# VCCINT_IO_BRAM_PS.net
KiCad netlist of a schematic drawn in Altium Designer
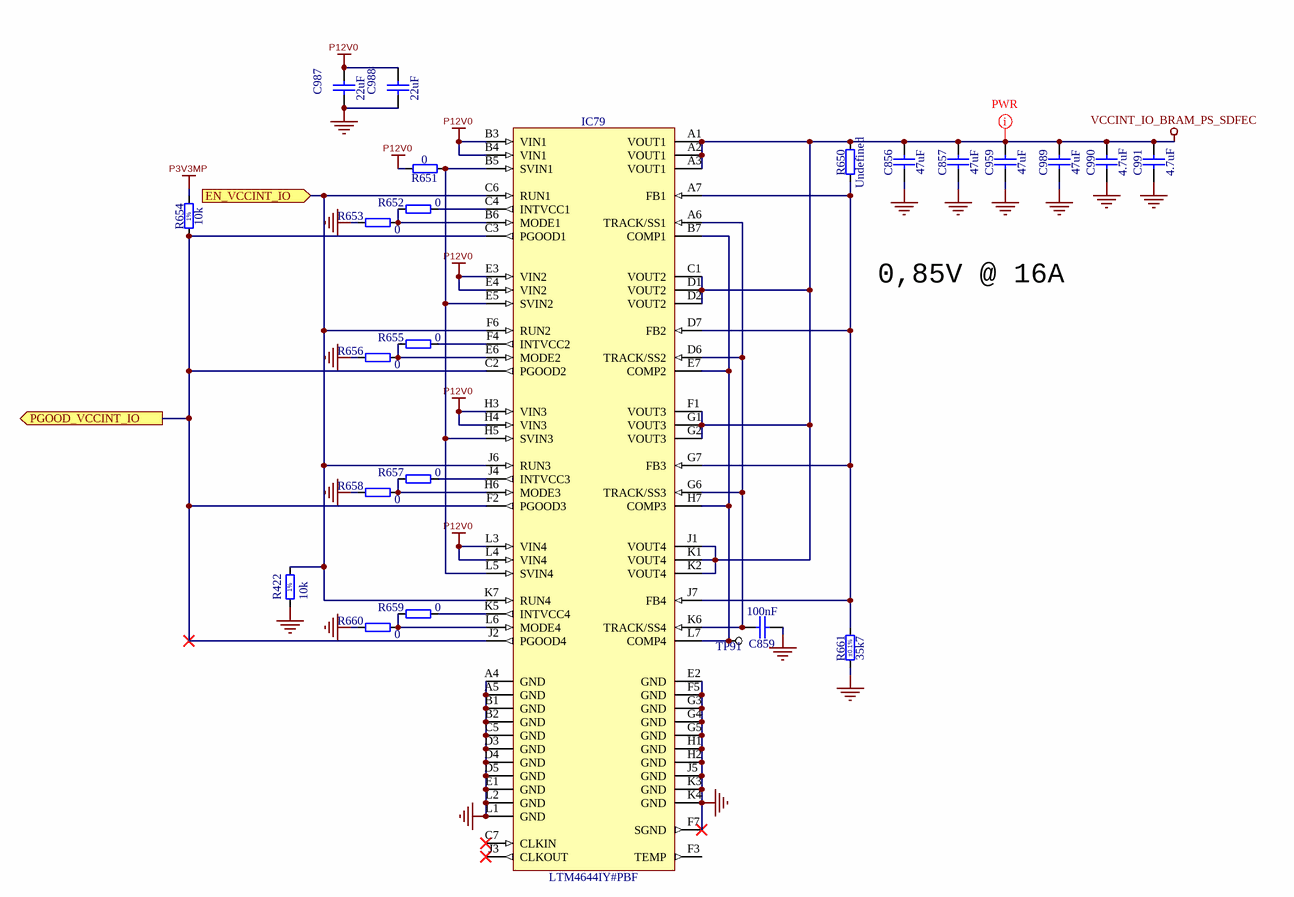
[diagram p0: VCCINT_IO_BRAM_PS.SchDoc]

(export (version "E")
  (design (tool "Eeschema 10.0.6"))
  (components
    (comp (ref "C856")
      (value "47uF")
      (footprint "CAPC2012X140N")
      (description "Non-polarised capacitor")
      (fields
        (field (name "MANUFACTURER PART NUMBER") "CC0805_47UF_6.3V_20%_X5R")
        (field (name "MANUFACTURER") "GENERIC")
        (field (name "AUTHOR") "CERN DEM JLC")
      )
      (libsource (lib "Capacitors") (part "Capacitor - non polarized"))
    )
    (comp (ref "C857")
      (value "47uF")
      (footprint "CAPC2012X140N")
      (description "Non-polarised capacitor")
      (fields
        (field (name "MANUFACTURER PART NUMBER") "CC0805_47UF_6.3V_20%_X5R")
        (field (name "MANUFACTURER") "GENERIC")
        (field (name "AUTHOR") "CERN DEM JLC")
      )
      (libsource (lib "Capacitors") (part "Capacitor - non polarized"))
    )
    (comp (ref "C859")
      (value "100nF")
      (footprint "CAPC1005X55N")
      (description "Non-polarised capacitor")
      (fields
        (field (name "PART NUMBER") "CC0402_100NF_16V_10%_X5R")
        (field (name "VOLTAGE") "16V")
        (field (name "AUTHOR") "CERN DEM JLC")
      )
      (libsource (lib "Capacitors") (part "Capacitor - non polarized"))
    )
    (comp (ref "C959")
      (value "47uF")
      (footprint "CAPC2012X140N")
      (description "Non-polarised capacitor")
      (fields
        (field (name "MANUFACTURER PART NUMBER") "CC0805_47UF_6.3V_20%_X5R")
        (field (name "MANUFACTURER") "GENERIC")
        (field (name "AUTHOR") "CERN DEM JLC")
      )
      (libsource (lib "Capacitors") (part "Capacitor - non polarized"))
    )
    (comp (ref "C987")
      (value "22uF")
      (footprint "CAPC2012X135N")
      (description "Non-polarised capacitor")
      (fields
        (field (name "MANUFACTURER PART NUMBER") "CC0805_22UF_16V_10%_X5R")
        (field (name "MANUFACTURER") "GENERIC")
        (field (name "AUTHOR") "CERN DEM JLC")
      )
      (libsource (lib "Capacitors") (part "Capacitor - non polarized"))
    )
    (comp (ref "C988")
      (value "22uF")
      (footprint "CAPC2012X135N")
      (description "Non-polarised capacitor")
      (fields
        (field (name "MANUFACTURER PART NUMBER") "CC0805_22UF_16V_10%_X5R")
        (field (name "MANUFACTURER") "GENERIC")
        (field (name "AUTHOR") "CERN DEM JLC")
      )
      (libsource (lib "Capacitors") (part "Capacitor - non polarized"))
    )
    (comp (ref "C989")
      (value "47uF")
      (footprint "CAPC2012X140N")
      (description "Non-polarised capacitor")
      (fields
        (field (name "MANUFACTURER PART NUMBER") "CC0805_47UF_6.3V_20%_X5R")
        (field (name "MANUFACTURER") "GENERIC")
        (field (name "AUTHOR") "CERN DEM JLC")
      )
      (libsource (lib "Capacitors") (part "Capacitor - non polarized"))
    )
    (comp (ref "C990")
      (value "4.7uF")
      (footprint "CAPC1709X95N")
      (description "Non-polarised capacitor")
      (fields
        (field (name "MANUFACTURER PART NUMBER") "CC0603_4.7UF_16V_10%_X5R")
        (field (name "MANUFACTURER") "GENERIC")
        (field (name "AUTHOR") "CERN DEM JLC")
      )
      (libsource (lib "Capacitors") (part "Capacitor - non polarized"))
    )
    (comp (ref "C991")
      (value "4.7uF")
      (footprint "CAPC1709X95N")
      (description "Non-polarised capacitor")
      (fields
        (field (name "MANUFACTURER PART NUMBER") "CC0603_4.7UF_16V_10%_X5R")
        (field (name "MANUFACTURER") "GENERIC")
        (field (name "AUTHOR") "CERN DEM JLC")
      )
      (libsource (lib "Capacitors") (part "Capacitor - non polarized"))
    )
    (comp (ref "IC79")
      (value "LTM4644IY#PBF")
      (footprint "BGA77C127P7X11_900X1500X521")
      (description "Quad DC/DC µModule Regulator with Configurable 4A Output Array")
      (fields (field (name "MANUFACTURER") "LINEAR TECHNOLOGY") (field (name "AUTHOR") "CERN DEM JLC"))
      (libsource (lib "ICs And Semiconductors") (part "LTM4644"))
    )
    (comp (ref "R422")
      (value "10k")
      (footprint "RESC1005X40N")
      (description "Resistor - 1%")
      (fields
        (field (name "MANUFACTURER PART NUMBER") "R0402_10K_1%_0.0625W_100PPM")
        (field (name "MANUFACTURER") "GENERIC")
        (field (name "AUTHOR") "CERN DEM JLC")
      )
      (libsource (lib "Resistors") (part "Resistor - 1%"))
    )
    (comp (ref "R650")
      (value "Undefined")
      (footprint "RESC1608X55N")
      (description "Resistor")
      (fields (field (name "PART NUMBER") "R0603_NO-VALUE") (field (name "AUTHOR") "CERN DEM JLC"))
      (libsource (lib "Resistors") (part "Resistor"))
    )
    (comp (ref "R651")
      (value "0")
      (footprint "RESC1005X40N")
      (description "Resistor")
      (fields
        (field (name "MANUFACTURER PART NUMBER") "R0402_0R_JUMPER")
        (field (name "MANUFACTURER") "GENERIC")
        (field (name "AUTHOR") "CERN DEM JLC")
      )
      (libsource (lib "Resistors") (part "Resistor"))
    )
    (comp (ref "R652")
      (value "0")
      (footprint "RESC1005X40N")
      (description "Resistor")
      (fields
        (field (name "MANUFACTURER PART NUMBER") "R0402_0R_JUMPER")
        (field (name "MANUFACTURER") "GENERIC")
        (field (name "AUTHOR") "CERN DEM JLC")
      )
      (libsource (lib "Resistors") (part "Resistor"))
    )
    (comp (ref "R653")
      (value "0")
      (footprint "RESC1005X40N")
      (description "Resistor")
      (fields
        (field (name "MANUFACTURER PART NUMBER") "R0402_0R_JUMPER")
        (field (name "MANUFACTURER") "GENERIC")
        (field (name "AUTHOR") "CERN DEM JLC")
      )
      (libsource (lib "Resistors") (part "Resistor"))
    )
    (comp (ref "R654")
      (value "10k")
      (footprint "RESC1005X40N")
      (description "Resistor - 1%")
      (fields
        (field (name "MANUFACTURER PART NUMBER") "R0402_10K_1%_0.0625W_100PPM")
        (field (name "MANUFACTURER") "GENERIC")
        (field (name "AUTHOR") "CERN DEM JLC")
      )
      (libsource (lib "Resistors") (part "Resistor - 1%"))
    )
    (comp (ref "R655")
      (value "0")
      (footprint "RESC1005X40N")
      (description "Resistor")
      (fields
        (field (name "MANUFACTURER PART NUMBER") "R0402_0R_JUMPER")
        (field (name "MANUFACTURER") "GENERIC")
        (field (name "AUTHOR") "CERN DEM JLC")
      )
      (libsource (lib "Resistors") (part "Resistor"))
    )
    (comp (ref "R656")
      (value "0")
      (footprint "RESC1005X40N")
      (description "Resistor")
      (fields
        (field (name "MANUFACTURER PART NUMBER") "R0402_0R_JUMPER")
        (field (name "MANUFACTURER") "GENERIC")
        (field (name "AUTHOR") "CERN DEM JLC")
      )
      (libsource (lib "Resistors") (part "Resistor"))
    )
    (comp (ref "R657")
      (value "0")
      (footprint "RESC1005X40N")
      (description "Resistor")
      (fields
        (field (name "MANUFACTURER PART NUMBER") "R0402_0R_JUMPER")
        (field (name "MANUFACTURER") "GENERIC")
        (field (name "AUTHOR") "CERN DEM JLC")
      )
      (libsource (lib "Resistors") (part "Resistor"))
    )
    (comp (ref "R658")
      (value "0")
      (footprint "RESC1005X40N")
      (description "Resistor")
      (fields
        (field (name "MANUFACTURER PART NUMBER") "R0402_0R_JUMPER")
        (field (name "MANUFACTURER") "GENERIC")
        (field (name "AUTHOR") "CERN DEM JLC")
      )
      (libsource (lib "Resistors") (part "Resistor"))
    )
    (comp (ref "R659")
      (value "0")
      (footprint "RESC1005X40N")
      (description "Resistor")
      (fields
        (field (name "MANUFACTURER PART NUMBER") "R0402_0R_JUMPER")
        (field (name "MANUFACTURER") "GENERIC")
        (field (name "AUTHOR") "CERN DEM JLC")
      )
      (libsource (lib "Resistors") (part "Resistor"))
    )
    (comp (ref "R660")
      (value "0")
      (footprint "RESC1005X40N")
      (description "Resistor")
      (fields
        (field (name "MANUFACTURER PART NUMBER") "R0402_0R_JUMPER")
        (field (name "MANUFACTURER") "GENERIC")
        (field (name "AUTHOR") "CERN DEM JLC")
      )
      (libsource (lib "Resistors") (part "Resistor"))
    )
    (comp (ref "R661")
      (value "35k7")
      (footprint "RESC1608X55N")
      (description "Resistor - 0.1%")
      (fields
        (field (name "TOLERANCE") "±0.1%")
        (field (name "PART NUMBER") "R0603_35K7_0.1%_0.063W_10PPM")
        (field (name "POWER") "0.063W")
        (field (name "AUTHOR") "CERN DEM JLC")
      )
      (libsource (lib "Resistors") (part "Resistor - 0.1%"))
    )
    (comp (ref "TP91")
      (value "TP")
      (footprint "TP")
      (description "Testpoint")
      (libsource (lib "LIBRARY_SCH") (part "TP"))
    )
  )
  (nets
    (net (code "1") (name "/EN_VCCINT_IO") (class "Default")
      (node (ref "IC79") (pin "C6") (pinfunction "RUN1_C6") (pintype "input"))
      (node (ref "IC79") (pin "F6") (pinfunction "RUN2_F6") (pintype "input"))
      (node (ref "IC79") (pin "J6") (pinfunction "RUN3_J6") (pintype "input"))
      (node (ref "IC79") (pin "K7") (pinfunction "RUN4_K7") (pintype "input"))
      (node (ref "R422") (pin "2") (pinfunction "2_2") (pintype "passive"))
    )
    (net (code "2") (name "/PGOOD_VCCINT_IO") (class "Default")
      (node (ref "IC79") (pin "C2") (pinfunction "PGOOD2_C2") (pintype "output"))
      (node (ref "IC79") (pin "C3") (pinfunction "PGOOD1_C3") (pintype "output"))
      (node (ref "IC79") (pin "F2") (pinfunction "PGOOD3_F2") (pintype "output"))
      (node (ref "IC79") (pin "J2") (pinfunction "PGOOD4_J2") (pintype "output"))
      (node (ref "R654") (pin "1") (pinfunction "1_1") (pintype "passive"))
    )
    (net (code "3") (name "GND") (class "Default")
      (node (ref "C856") (pin "1") (pinfunction "1_1") (pintype "passive"))
      (node (ref "C857") (pin "1") (pinfunction "1_1") (pintype "passive"))
      (node (ref "C859") (pin "1") (pinfunction "1_1") (pintype "passive"))
      (node (ref "C959") (pin "1") (pinfunction "1_1") (pintype "passive"))
      (node (ref "C987") (pin "1") (pinfunction "1_1") (pintype "passive"))
      (node (ref "C988") (pin "1") (pinfunction "1_1") (pintype "passive"))
      (node (ref "C989") (pin "1") (pinfunction "1_1") (pintype "passive"))
      (node (ref "C990") (pin "1") (pinfunction "1_1") (pintype "passive"))
      (node (ref "C991") (pin "1") (pinfunction "1_1") (pintype "passive"))
      (node (ref "IC79") (pin "A4") (pinfunction "GND_A4") (pintype "power_in"))
      (node (ref "IC79") (pin "A5") (pinfunction "GND_A5") (pintype "power_in"))
      (node (ref "IC79") (pin "B1") (pinfunction "GND_B1") (pintype "power_in"))
      (node (ref "IC79") (pin "B2") (pinfunction "GND_B2") (pintype "power_in"))
      (node (ref "IC79") (pin "C5") (pinfunction "GND_C5") (pintype "power_in"))
      (node (ref "IC79") (pin "D3") (pinfunction "GND_D3") (pintype "power_in"))
      (node (ref "IC79") (pin "D4") (pinfunction "GND_D4") (pintype "power_in"))
      (node (ref "IC79") (pin "D5") (pinfunction "GND_D5") (pintype "power_in"))
      (node (ref "IC79") (pin "E1") (pinfunction "GND_E1") (pintype "power_in"))
      (node (ref "IC79") (pin "E2") (pinfunction "GND_E2") (pintype "power_in"))
      (node (ref "IC79") (pin "F5") (pinfunction "GND_F5") (pintype "power_in"))
      (node (ref "IC79") (pin "F7") (pinfunction "SGND_F7") (pintype "output"))
      (node (ref "IC79") (pin "G3") (pinfunction "GND_G3") (pintype "power_in"))
      (node (ref "IC79") (pin "G4") (pinfunction "GND_G4") (pintype "power_in"))
      (node (ref "IC79") (pin "G5") (pinfunction "GND_G5") (pintype "power_in"))
      (node (ref "IC79") (pin "H1") (pinfunction "GND_H1") (pintype "power_in"))
      (node (ref "IC79") (pin "H2") (pinfunction "GND_H2") (pintype "power_in"))
      (node (ref "IC79") (pin "J5") (pinfunction "GND_J5") (pintype "power_in"))
      (node (ref "IC79") (pin "K3") (pinfunction "GND_K3") (pintype "power_in"))
      (node (ref "IC79") (pin "K4") (pinfunction "GND_K4") (pintype "power_in"))
      (node (ref "IC79") (pin "L1") (pinfunction "GND_L1") (pintype "power_in"))
      (node (ref "IC79") (pin "L2") (pinfunction "GND_L2") (pintype "power_in"))
      (node (ref "R422") (pin "1") (pinfunction "1_1") (pintype "passive"))
      (node (ref "R653") (pin "2") (pinfunction "2_2") (pintype "passive"))
      (node (ref "R656") (pin "2") (pinfunction "2_2") (pintype "passive"))
      (node (ref "R658") (pin "2") (pinfunction "2_2") (pintype "passive"))
      (node (ref "R660") (pin "2") (pinfunction "2_2") (pintype "passive"))
      (node (ref "R661") (pin "1") (pinfunction "1_1") (pintype "passive"))
    )
    (net (code "4") (name "Net-(IC79-COMP1)") (class "Default")
      (node (ref "IC79") (pin "B7") (pinfunction "COMP1_B7") (pintype "passive"))
      (node (ref "IC79") (pin "E7") (pinfunction "COMP2_E7") (pintype "passive"))
      (node (ref "IC79") (pin "H7") (pinfunction "COMP3_H7") (pintype "passive"))
      (node (ref "IC79") (pin "L7") (pinfunction "COMP4_L7") (pintype "passive"))
      (node (ref "TP91") (pin "1") (pintype "passive"))
    )
    (net (code "5") (name "Net-(IC79-FB1)") (class "Default")
      (node (ref "IC79") (pin "A7") (pinfunction "FB1_A7") (pintype "input"))
      (node (ref "IC79") (pin "D7") (pinfunction "FB2_D7") (pintype "input"))
      (node (ref "IC79") (pin "G7") (pinfunction "FB3_G7") (pintype "input"))
      (node (ref "IC79") (pin "J7") (pinfunction "FB4_J7") (pintype "input"))
      (node (ref "R650") (pin "1") (pinfunction "1_1") (pintype "passive"))
      (node (ref "R661") (pin "2") (pinfunction "2_2") (pintype "passive"))
    )
    (net (code "6") (name "Net-(IC79-INTVCC1)") (class "Default")
      (node (ref "IC79") (pin "C4") (pinfunction "INTVCC1_C4") (pintype "output"))
      (node (ref "R652") (pin "1") (pinfunction "1_1") (pintype "passive"))
    )
    (net (code "7") (name "Net-(IC79-INTVCC2)") (class "Default")
      (node (ref "IC79") (pin "F4") (pinfunction "INTVCC2_F4") (pintype "output"))
      (node (ref "R655") (pin "1") (pinfunction "1_1") (pintype "passive"))
    )
    (net (code "8") (name "Net-(IC79-INTVCC3)") (class "Default")
      (node (ref "IC79") (pin "J4") (pinfunction "INTVCC3_J4") (pintype "output"))
      (node (ref "R657") (pin "1") (pinfunction "1_1") (pintype "passive"))
    )
    (net (code "9") (name "Net-(IC79-INTVCC4)") (class "Default")
      (node (ref "IC79") (pin "K5") (pinfunction "INTVCC4_K5") (pintype "output"))
      (node (ref "R659") (pin "1") (pinfunction "1_1") (pintype "passive"))
    )
    (net (code "10") (name "Net-(IC79-MODE1)") (class "Default")
      (node (ref "IC79") (pin "B6") (pinfunction "MODE1_B6") (pintype "input"))
      (node (ref "R652") (pin "2") (pinfunction "2_2") (pintype "passive"))
      (node (ref "R653") (pin "1") (pinfunction "1_1") (pintype "passive"))
    )
    (net (code "11") (name "Net-(IC79-MODE2)") (class "Default")
      (node (ref "IC79") (pin "E6") (pinfunction "MODE2_E6") (pintype "input"))
      (node (ref "R655") (pin "2") (pinfunction "2_2") (pintype "passive"))
      (node (ref "R656") (pin "1") (pinfunction "1_1") (pintype "passive"))
    )
    (net (code "12") (name "Net-(IC79-MODE3)") (class "Default")
      (node (ref "IC79") (pin "H6") (pinfunction "MODE3_H6") (pintype "input"))
      (node (ref "R657") (pin "2") (pinfunction "2_2") (pintype "passive"))
      (node (ref "R658") (pin "1") (pinfunction "1_1") (pintype "passive"))
    )
    (net (code "13") (name "Net-(IC79-MODE4)") (class "Default")
      (node (ref "IC79") (pin "L6") (pinfunction "MODE4_L6") (pintype "input"))
      (node (ref "R659") (pin "2") (pinfunction "2_2") (pintype "passive"))
      (node (ref "R660") (pin "1") (pinfunction "1_1") (pintype "passive"))
    )
    (net (code "14") (name "Net-(IC79-SVIN1)") (class "Default")
      (node (ref "IC79") (pin "B5") (pinfunction "SVIN1_B5") (pintype "input"))
      (node (ref "IC79") (pin "E5") (pinfunction "SVIN2_E5") (pintype "input"))
      (node (ref "IC79") (pin "H5") (pinfunction "SVIN3_H5") (pintype "input"))
      (node (ref "IC79") (pin "L5") (pinfunction "SVIN4_L5") (pintype "input"))
      (node (ref "R651") (pin "1") (pinfunction "1_1") (pintype "passive"))
    )
    (net (code "15") (name "Net-(IC79-TRACK{slash}SS1)") (class "Default")
      (node (ref "C859") (pin "2") (pinfunction "2_2") (pintype "passive"))
      (node (ref "IC79") (pin "A6") (pinfunction "TRACK/SS1_A6") (pintype "input"))
      (node (ref "IC79") (pin "D6") (pinfunction "TRACK/SS2_D6") (pintype "input"))
      (node (ref "IC79") (pin "G6") (pinfunction "TRACK/SS3_G6") (pintype "input"))
      (node (ref "IC79") (pin "K6") (pinfunction "TRACK/SS4_K6") (pintype "input"))
    )
    (net (code "16") (name "P3V3MP") (class "Default")
      (node (ref "R654") (pin "2") (pinfunction "2_2") (pintype "passive"))
    )
    (net (code "17") (name "P12V0") (class "Default")
      (node (ref "C987") (pin "2") (pinfunction "2_2") (pintype "passive"))
      (node (ref "C988") (pin "2") (pinfunction "2_2") (pintype "passive"))
      (node (ref "IC79") (pin "B3") (pinfunction "VIN1_B3") (pintype "input"))
      (node (ref "IC79") (pin "B4") (pinfunction "VIN1_B4") (pintype "input"))
      (node (ref "IC79") (pin "E3") (pinfunction "VIN2_E3") (pintype "input"))
      (node (ref "IC79") (pin "E4") (pinfunction "VIN2_E4") (pintype "input"))
      (node (ref "IC79") (pin "H3") (pinfunction "VIN3_H3") (pintype "input"))
      (node (ref "IC79") (pin "H4") (pinfunction "VIN3_H4") (pintype "input"))
      (node (ref "IC79") (pin "L3") (pinfunction "VIN4_L3") (pintype "input"))
      (node (ref "IC79") (pin "L4") (pinfunction "VIN4_L4") (pintype "input"))
      (node (ref "R651") (pin "2") (pinfunction "2_2") (pintype "passive"))
    )
    (net (code "18") (name "VCCINT_IO_BRAM_PS_SDFEC") (class "Default")
      (node (ref "C856") (pin "2") (pinfunction "2_2") (pintype "passive"))
      (node (ref "C857") (pin "2") (pinfunction "2_2") (pintype "passive"))
      (node (ref "C959") (pin "2") (pinfunction "2_2") (pintype "passive"))
      (node (ref "C989") (pin "2") (pinfunction "2_2") (pintype "passive"))
      (node (ref "C990") (pin "2") (pinfunction "2_2") (pintype "passive"))
      (node (ref "C991") (pin "2") (pinfunction "2_2") (pintype "passive"))
      (node (ref "IC79") (pin "A1") (pinfunction "VOUT1_A1") (pintype "power_in"))
      (node (ref "IC79") (pin "A2") (pinfunction "VOUT1_A2") (pintype "power_in"))
      (node (ref "IC79") (pin "A3") (pinfunction "VOUT1_A3") (pintype "power_in"))
      (node (ref "IC79") (pin "C1") (pinfunction "VOUT2_C1") (pintype "power_in"))
      (node (ref "IC79") (pin "D1") (pinfunction "VOUT2_D1") (pintype "power_in"))
      (node (ref "IC79") (pin "D2") (pinfunction "VOUT2_D2") (pintype "power_in"))
      (node (ref "IC79") (pin "F1") (pinfunction "VOUT3_F1") (pintype "power_in"))
      (node (ref "IC79") (pin "G1") (pinfunction "VOUT3_G1") (pintype "power_in"))
      (node (ref "IC79") (pin "G2") (pinfunction "VOUT3_G2") (pintype "power_in"))
      (node (ref "IC79") (pin "J1") (pinfunction "VOUT4_J1") (pintype "power_in"))
      (node (ref "IC79") (pin "K1") (pinfunction "VOUT4_K1") (pintype "power_in"))
      (node (ref "IC79") (pin "K2") (pinfunction "VOUT4_K2") (pintype "power_in"))
      (node (ref "R650") (pin "2") (pinfunction "2_2") (pintype "passive"))
    )
    (net (code "19") (name "unconnected-(IC79-CLKIN-PadC7)") (class "Default")
      (node (ref "IC79") (pin "C7") (pinfunction "CLKIN_C7") (pintype "input+no_connect"))
    )
    (net (code "20") (name "unconnected-(IC79-CLKOUT-PadJ3)") (class "Default")
      (node (ref "IC79") (pin "J3") (pinfunction "CLKOUT_J3") (pintype "output+no_connect"))
    )
    (net (code "21") (name "unconnected-(IC79-TEMP-PadF3)") (class "Default")
      (node (ref "IC79") (pin "F3") (pinfunction "TEMP_F3") (pintype "output"))
    )
  )
)
